# Endonasal_Module_Breakout_rev1.net
KiCad netlist of a schematic drawn in EAGLE
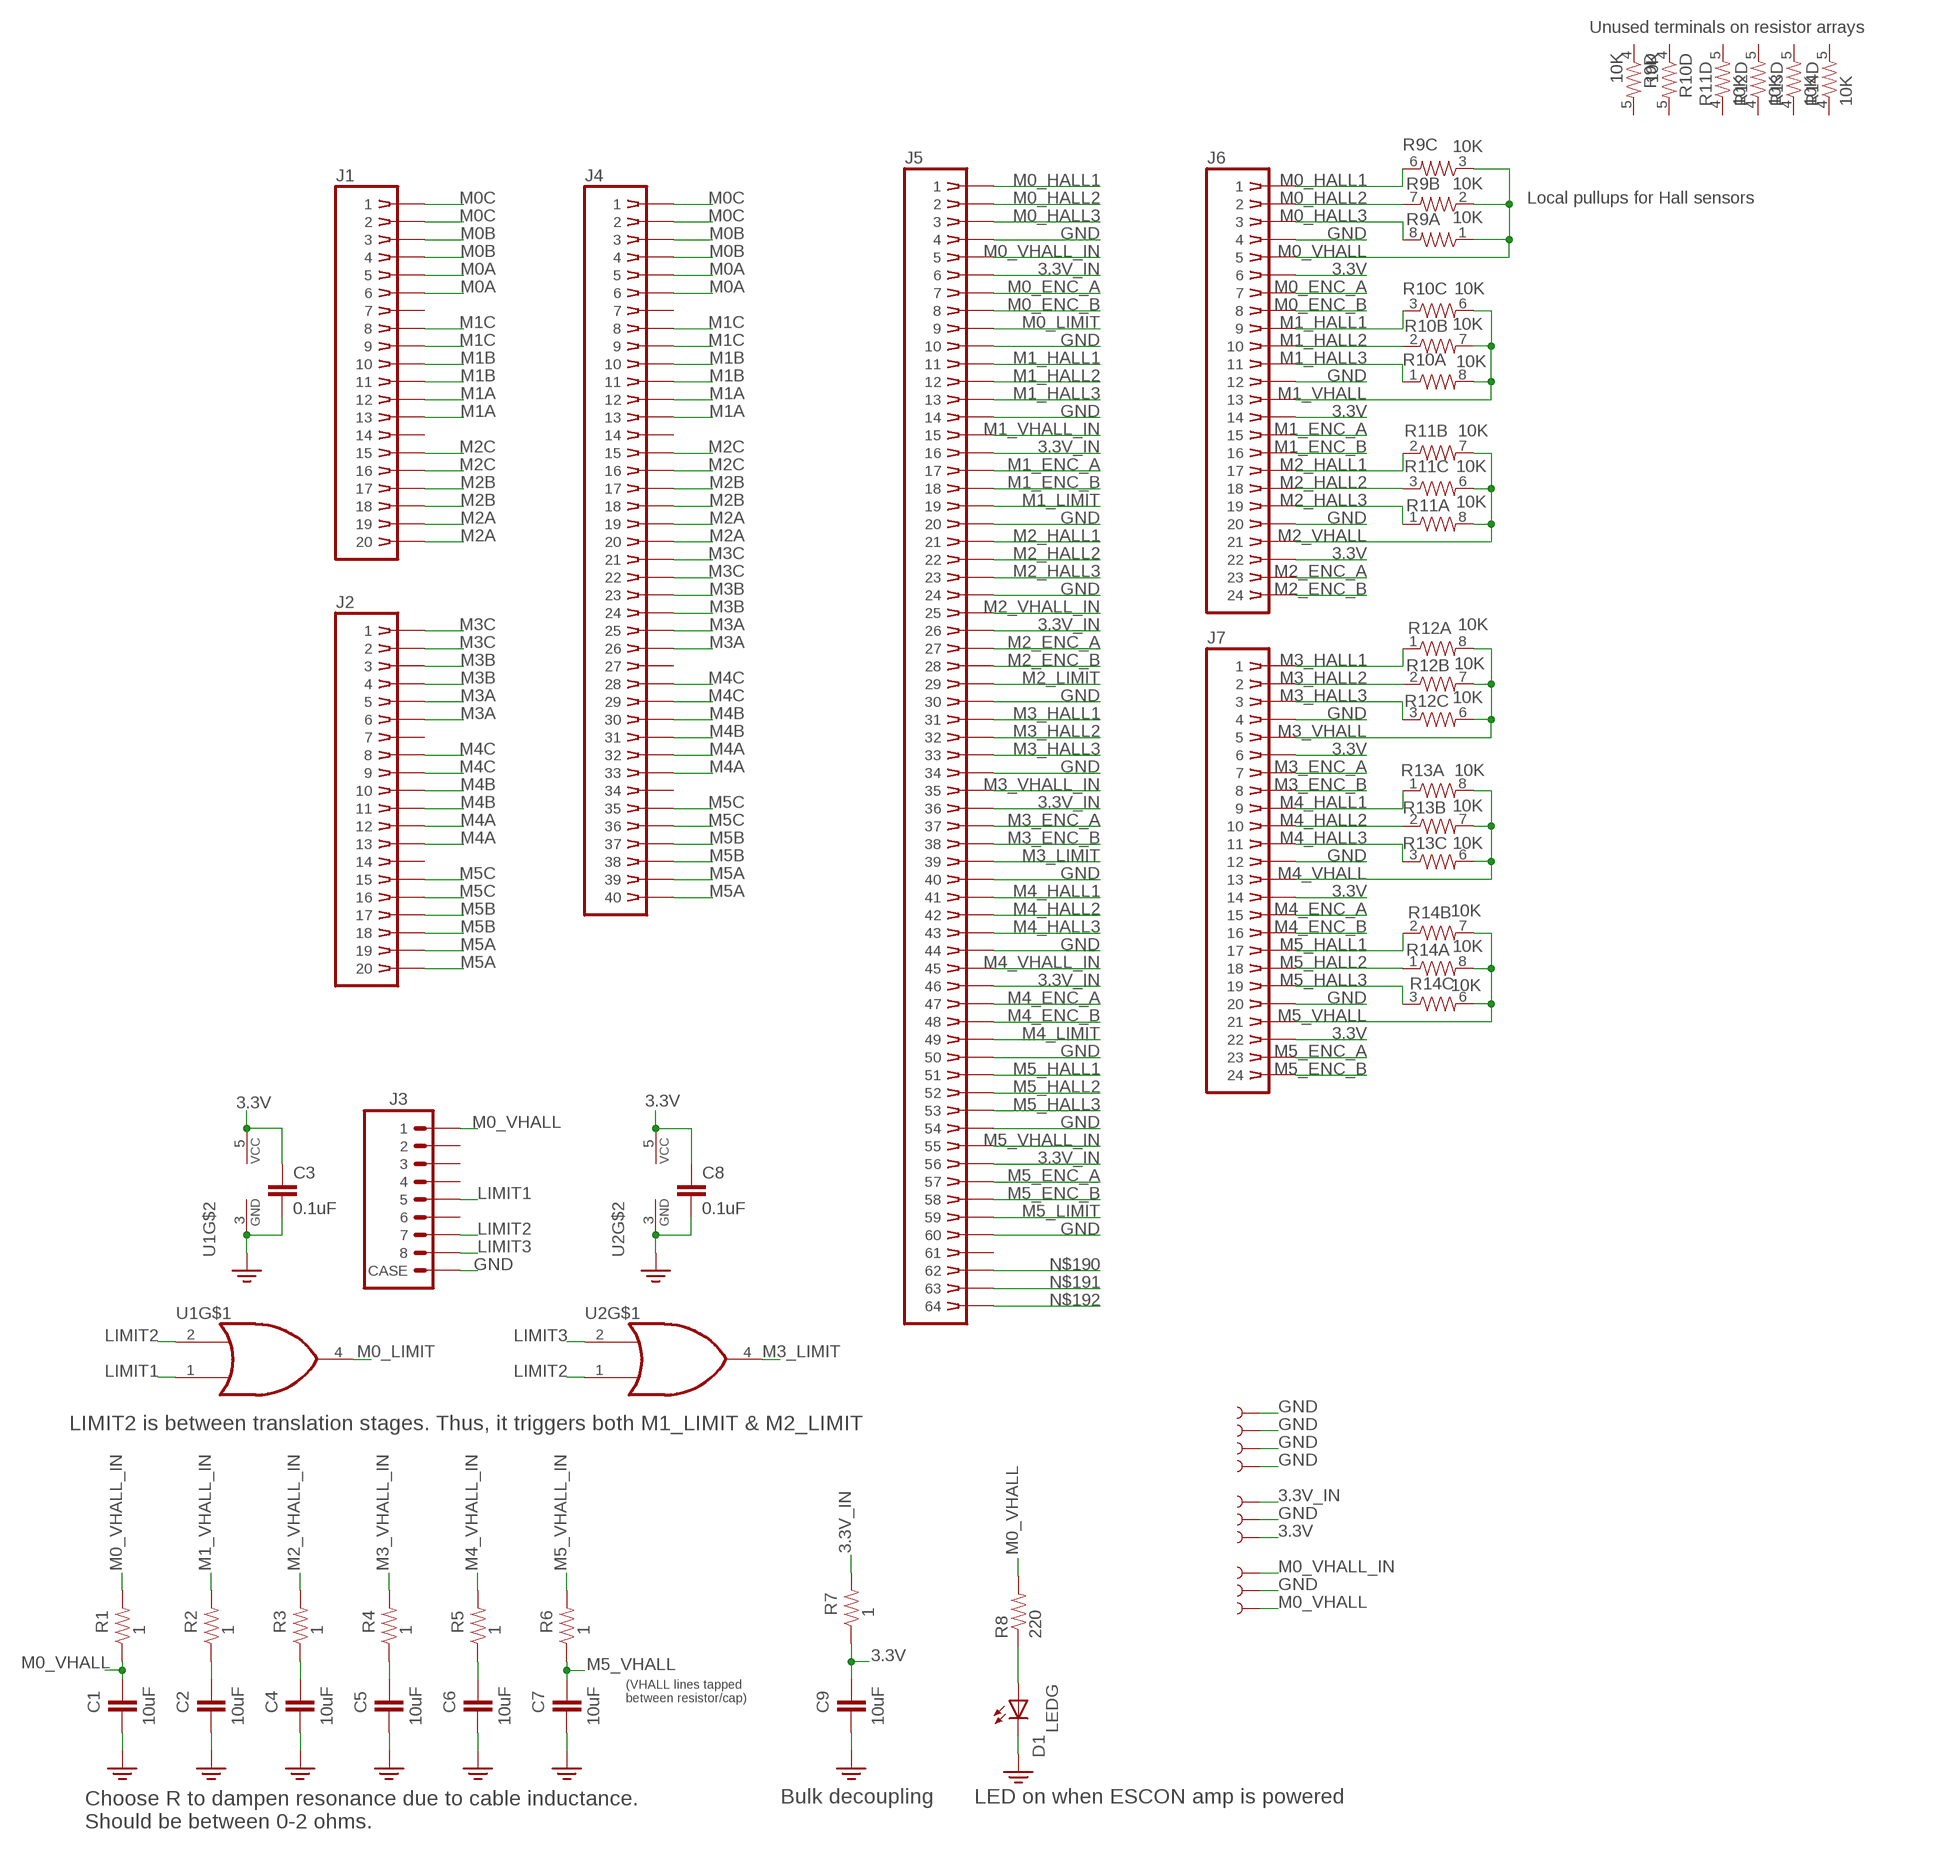
[diagram p0: schematic, sheet 1]

(export (version "E")
  (design (tool "Eeschema 10.0.6"))
  (components
    (comp (ref "3.3V")
      (value "TEST-POINT_5021")
      (footprint "eagle-import:TEST-POINT_5021")
      (libsource (lib "eagle-import") (part "TEST-POINT_5021"))
    )
    (comp (ref "3.3V-IN")
      (value "TEST-POINT_5021")
      (footprint "eagle-import:TEST-POINT_5021")
      (libsource (lib "eagle-import") (part "TEST-POINT_5021"))
    )
    (comp (ref "5V")
      (value "TEST-POINT_5021")
      (footprint "eagle-import:TEST-POINT_5021")
      (libsource (lib "eagle-import") (part "TEST-POINT_5021"))
    )
    (comp (ref "5V-IN")
      (value "TEST-POINT_5021")
      (footprint "eagle-import:TEST-POINT_5021")
      (libsource (lib "eagle-import") (part "TEST-POINT_5021"))
    )
    (comp (ref "C1")
      (value "10uF")
      (footprint "eagle-import:C0805K")
      (libsource (lib "eagle-import") (part "CAP0805"))
    )
    (comp (ref "C2")
      (value "10uF")
      (footprint "eagle-import:C0805K")
      (libsource (lib "eagle-import") (part "CAP0805"))
    )
    (comp (ref "C3")
      (value "0.1uF")
      (footprint "eagle-import:0603-CAP")
      (libsource (lib "eagle-import") (part "CAP0603-CAP"))
    )
    (comp (ref "C4")
      (value "10uF")
      (footprint "eagle-import:C0805K")
      (libsource (lib "eagle-import") (part "CAP0805"))
    )
    (comp (ref "C5")
      (value "10uF")
      (footprint "eagle-import:C0805K")
      (libsource (lib "eagle-import") (part "CAP0805"))
    )
    (comp (ref "C6")
      (value "10uF")
      (footprint "eagle-import:C0805K")
      (libsource (lib "eagle-import") (part "CAP0805"))
    )
    (comp (ref "C7")
      (value "10uF")
      (footprint "eagle-import:C0805K")
      (libsource (lib "eagle-import") (part "CAP0805"))
    )
    (comp (ref "C8")
      (value "0.1uF")
      (footprint "eagle-import:0603-CAP")
      (libsource (lib "eagle-import") (part "CAP0603-CAP"))
    )
    (comp (ref "C9")
      (value "10uF")
      (footprint "eagle-import:C0805K")
      (libsource (lib "eagle-import") (part "CAP0805"))
    )
    (comp (ref "D1")
      (value "LEDG")
      (footprint "eagle-import:LED-0805")
      (libsource (lib "eagle-import") (part "LED-0805"))
    )
    (comp (ref "GND")
      (value "TEST-POINT_5021")
      (footprint "eagle-import:TEST-POINT_5021")
      (libsource (lib "eagle-import") (part "TEST-POINT_5021"))
    )
    (comp (ref "J1")
      (value "CONN_RECT_2X10TH")
      (footprint "eagle-import:CONN_IDC_20_MALE_TH")
      (libsource (lib "eagle-import") (part "CONN_RECT_2X10TH"))
    )
    (comp (ref "J2")
      (value "CONN_RECT_2X10TH")
      (footprint "eagle-import:CONN_IDC_20_MALE_TH")
      (libsource (lib "eagle-import") (part "CONN_RECT_2X10TH"))
    )
    (comp (ref "J3")
      (value "JACK_8P8C_RJ45_ETHERNET")
      (footprint "eagle-import:ETHERNET_A104932")
      (libsource (lib "eagle-import") (part "JACK_8P8C_RJ45_ETHERNET"))
    )
    (comp (ref "J4")
      (value "CONN_RECT_2X20TH")
      (footprint "eagle-import:CONN_IDC_40_MALE_TH")
      (libsource (lib "eagle-import") (part "CONN_RECT_2X20TH"))
    )
    (comp (ref "J5")
      (value "CONN_RECT_2X32NOHOLES")
      (footprint "eagle-import:CONN_IDC_64_MALE_TH_NOHOLES")
      (libsource (lib "eagle-import") (part "CONN_RECT_2X32NOHOLES"))
    )
    (comp (ref "J6")
      (value "CONN_RECT_2X12TH")
      (footprint "eagle-import:CONN_IDC_24_MALE_TH")
      (libsource (lib "eagle-import") (part "CONN_RECT_2X12TH"))
    )
    (comp (ref "J7")
      (value "CONN_RECT_2X12TH")
      (footprint "eagle-import:CONN_IDC_24_MALE_TH")
      (libsource (lib "eagle-import") (part "CONN_RECT_2X12TH"))
    )
    (comp (ref "R1")
      (value "1")
      (footprint "eagle-import:0603-RES")
      (libsource (lib "eagle-import") (part "RESISTOR-0603"))
    )
    (comp (ref "R2")
      (value "1")
      (footprint "eagle-import:0603-RES")
      (libsource (lib "eagle-import") (part "RESISTOR-0603"))
    )
    (comp (ref "R3")
      (value "1")
      (footprint "eagle-import:0603-RES")
      (libsource (lib "eagle-import") (part "RESISTOR-0603"))
    )
    (comp (ref "R4")
      (value "1")
      (footprint "eagle-import:0603-RES")
      (libsource (lib "eagle-import") (part "RESISTOR-0603"))
    )
    (comp (ref "R5")
      (value "1")
      (footprint "eagle-import:0603-RES")
      (libsource (lib "eagle-import") (part "RESISTOR-0603"))
    )
    (comp (ref "R6")
      (value "1")
      (footprint "eagle-import:0603-RES")
      (libsource (lib "eagle-import") (part "RESISTOR-0603"))
    )
    (comp (ref "R7")
      (value "1")
      (footprint "eagle-import:0603-RES")
      (libsource (lib "eagle-import") (part "RESISTOR-0603"))
    )
    (comp (ref "R8")
      (value "220")
      (footprint "eagle-import:0603-RES")
      (libsource (lib "eagle-import") (part "RESISTOR-0603"))
    )
    (comp (ref "R9")
      (value "10K")
      (footprint "eagle-import:0603-ARV")
      (libsource (lib "eagle-import") (part "RESISTOR-ARRAY0603-ARV"))
    )
    (comp (ref "R10")
      (value "10K")
      (footprint "eagle-import:0603-ARV")
      (libsource (lib "eagle-import") (part "RESISTOR-ARRAY0603-ARV"))
    )
    (comp (ref "R11")
      (value "10K")
      (footprint "eagle-import:0603-ARV")
      (libsource (lib "eagle-import") (part "RESISTOR-ARRAY0603-ARV"))
    )
    (comp (ref "R12")
      (value "10K")
      (footprint "eagle-import:0603-ARV")
      (libsource (lib "eagle-import") (part "RESISTOR-ARRAY0603-ARV"))
    )
    (comp (ref "R13")
      (value "10K")
      (footprint "eagle-import:0603-ARV")
      (libsource (lib "eagle-import") (part "RESISTOR-ARRAY0603-ARV"))
    )
    (comp (ref "R14")
      (value "10K")
      (footprint "eagle-import:0603-ARV")
      (libsource (lib "eagle-import") (part "RESISTOR-ARRAY0603-ARV"))
    )
    (comp (ref "TP5")
      (value "TEST-POINT_5021")
      (footprint "eagle-import:TEST-POINT_5021")
      (libsource (lib "eagle-import") (part "TEST-POINT_5021"))
    )
    (comp (ref "TP7")
      (value "TEST-POINT3X5")
      (footprint "eagle-import:PAD.03X.05")
      (libsource (lib "eagle-import") (part "TEST-POINT3X5"))
    )
    (comp (ref "TP8")
      (value "TEST-POINT3X5")
      (footprint "eagle-import:PAD.03X.05")
      (libsource (lib "eagle-import") (part "TEST-POINT3X5"))
    )
    (comp (ref "TP9")
      (value "TEST-POINT3X5")
      (footprint "eagle-import:PAD.03X.05")
      (libsource (lib "eagle-import") (part "TEST-POINT3X5"))
    )
    (comp (ref "TP10")
      (value "TEST-POINT3X5")
      (footprint "eagle-import:PAD.03X.05")
      (libsource (lib "eagle-import") (part "TEST-POINT3X5"))
    )
    (comp (ref "U1")
      (value "OR_M0")
      (footprint "eagle-import:SOT353")
      (libsource (lib "eagle-import") (part "OR"))
    )
    (comp (ref "U2")
      (value "OR_M3")
      (footprint "eagle-import:SOT353")
      (libsource (lib "eagle-import") (part "OR"))
    )
  )
  (nets
    (net (code "1") (name "/3.3V") (class "Default")
      (node (ref "3.3V") (pin "P$1") (pinfunction "1_P$1") (pintype "bidirectional"))
      (node (ref "C3") (pin "1") (pinfunction "1_1") (pintype "passive"))
      (node (ref "C8") (pin "1") (pinfunction "1_1") (pintype "passive"))
      (node (ref "C9") (pin "1") (pinfunction "1_1") (pintype "passive"))
      (node (ref "J6") (pin "P$14") (pinfunction "14_P$14") (pintype "passive"))
      (node (ref "J6") (pin "P$22") (pinfunction "22_P$22") (pintype "passive"))
      (node (ref "J6") (pin "P$6") (pinfunction "6_P$6") (pintype "passive"))
      (node (ref "J7") (pin "P$14") (pinfunction "14_P$14") (pintype "passive"))
      (node (ref "J7") (pin "P$22") (pinfunction "22_P$22") (pintype "passive"))
      (node (ref "J7") (pin "P$6") (pinfunction "6_P$6") (pintype "passive"))
      (node (ref "R7") (pin "1") (pinfunction "1_1") (pintype "passive"))
      (node (ref "U1") (pin "5") (pinfunction "VCC_5") (pintype "power_in"))
      (node (ref "U2") (pin "5") (pinfunction "VCC_5") (pintype "power_in"))
    )
    (net (code "2") (name "/3.3V_IN") (class "Default")
      (node (ref "3.3V-IN") (pin "P$1") (pinfunction "1_P$1") (pintype "bidirectional"))
      (node (ref "J5") (pin "P$16") (pinfunction "16_P$16") (pintype "passive"))
      (node (ref "J5") (pin "P$26") (pinfunction "26_P$26") (pintype "passive"))
      (node (ref "J5") (pin "P$36") (pinfunction "36_P$36") (pintype "passive"))
      (node (ref "J5") (pin "P$46") (pinfunction "46_P$46") (pintype "passive"))
      (node (ref "J5") (pin "P$56") (pinfunction "56_P$56") (pintype "passive"))
      (node (ref "J5") (pin "P$6") (pinfunction "6_P$6") (pintype "passive"))
      (node (ref "R7") (pin "2") (pinfunction "2_2") (pintype "passive"))
    )
    (net (code "3") (name "/LIMIT1") (class "Default")
      (node (ref "J3") (pin "P$5") (pinfunction "5_P$5") (pintype "passive"))
      (node (ref "U1") (pin "1") (pinfunction "B_1") (pintype "input"))
    )
    (net (code "4") (name "/LIMIT2") (class "Default")
      (node (ref "J3") (pin "P$7") (pinfunction "7_P$7") (pintype "passive"))
      (node (ref "U1") (pin "2") (pinfunction "A_2") (pintype "input"))
      (node (ref "U2") (pin "1") (pinfunction "B_1") (pintype "input"))
    )
    (net (code "5") (name "/LIMIT3") (class "Default")
      (node (ref "J3") (pin "P$8") (pinfunction "8_P$8") (pintype "passive"))
      (node (ref "U2") (pin "2") (pinfunction "A_2") (pintype "input"))
    )
    (net (code "6") (name "/M0A") (class "Default")
      (node (ref "J1") (pin "P$5") (pinfunction "5_P$5") (pintype "passive"))
      (node (ref "J1") (pin "P$6") (pinfunction "6_P$6") (pintype "passive"))
      (node (ref "J4") (pin "P$5") (pinfunction "5_P$5") (pintype "passive"))
      (node (ref "J4") (pin "P$6") (pinfunction "6_P$6") (pintype "passive"))
    )
    (net (code "7") (name "/M0B") (class "Default")
      (node (ref "J1") (pin "P$3") (pinfunction "3_P$3") (pintype "passive"))
      (node (ref "J1") (pin "P$4") (pinfunction "4_P$4") (pintype "passive"))
      (node (ref "J4") (pin "P$3") (pinfunction "3_P$3") (pintype "passive"))
      (node (ref "J4") (pin "P$4") (pinfunction "4_P$4") (pintype "passive"))
    )
    (net (code "8") (name "/M0C") (class "Default")
      (node (ref "J1") (pin "P$1") (pinfunction "1_P$1") (pintype "passive"))
      (node (ref "J1") (pin "P$2") (pinfunction "2_P$2") (pintype "passive"))
      (node (ref "J4") (pin "P$1") (pinfunction "1_P$1") (pintype "passive"))
      (node (ref "J4") (pin "P$2") (pinfunction "2_P$2") (pintype "passive"))
    )
    (net (code "9") (name "/M0_ENC_A") (class "Default")
      (node (ref "J5") (pin "P$7") (pinfunction "7_P$7") (pintype "passive"))
      (node (ref "J6") (pin "P$7") (pinfunction "7_P$7") (pintype "passive"))
    )
    (net (code "10") (name "/M0_ENC_B") (class "Default")
      (node (ref "J5") (pin "P$8") (pinfunction "8_P$8") (pintype "passive"))
      (node (ref "J6") (pin "P$8") (pinfunction "8_P$8") (pintype "passive"))
    )
    (net (code "11") (name "/M0_HALL1") (class "Default")
      (node (ref "J5") (pin "P$1") (pinfunction "1_P$1") (pintype "passive"))
      (node (ref "J6") (pin "P$1") (pinfunction "1_P$1") (pintype "passive"))
      (node (ref "R9") (pin "6") (pinfunction "2_6") (pintype "passive"))
    )
    (net (code "12") (name "/M0_HALL2") (class "Default")
      (node (ref "J5") (pin "P$2") (pinfunction "2_P$2") (pintype "passive"))
      (node (ref "J6") (pin "P$2") (pinfunction "2_P$2") (pintype "passive"))
      (node (ref "R9") (pin "7") (pinfunction "2_7") (pintype "passive"))
    )
    (net (code "13") (name "/M0_HALL3") (class "Default")
      (node (ref "J5") (pin "P$3") (pinfunction "3_P$3") (pintype "passive"))
      (node (ref "J6") (pin "P$3") (pinfunction "3_P$3") (pintype "passive"))
      (node (ref "R9") (pin "8") (pinfunction "2_8") (pintype "passive"))
    )
    (net (code "14") (name "/M0_LIMIT") (class "Default")
      (node (ref "J5") (pin "P$9") (pinfunction "9_P$9") (pintype "passive"))
      (node (ref "U1") (pin "4") (pinfunction "Y_4") (pintype "output"))
    )
    (net (code "15") (name "/M0_VHALL") (class "Default")
      (node (ref "5V") (pin "P$1") (pinfunction "1_P$1") (pintype "bidirectional"))
      (node (ref "C1") (pin "1") (pinfunction "1_1") (pintype "passive"))
      (node (ref "J3") (pin "P$1") (pinfunction "1_P$1") (pintype "passive"))
      (node (ref "J6") (pin "P$5") (pinfunction "5_P$5") (pintype "passive"))
      (node (ref "R1") (pin "1") (pinfunction "1_1") (pintype "passive"))
      (node (ref "R8") (pin "2") (pinfunction "2_2") (pintype "passive"))
      (node (ref "R9") (pin "1") (pinfunction "1_1") (pintype "passive"))
      (node (ref "R9") (pin "2") (pinfunction "1_2") (pintype "passive"))
      (node (ref "R9") (pin "3") (pinfunction "1_3") (pintype "passive"))
    )
    (net (code "16") (name "/M0_VHALL_IN") (class "Default")
      (node (ref "5V-IN") (pin "P$1") (pinfunction "1_P$1") (pintype "bidirectional"))
      (node (ref "J5") (pin "P$5") (pinfunction "5_P$5") (pintype "passive"))
      (node (ref "R1") (pin "2") (pinfunction "2_2") (pintype "passive"))
    )
    (net (code "17") (name "/M1A") (class "Default")
      (node (ref "J1") (pin "P$12") (pinfunction "12_P$12") (pintype "passive"))
      (node (ref "J1") (pin "P$13") (pinfunction "13_P$13") (pintype "passive"))
      (node (ref "J4") (pin "P$12") (pinfunction "12_P$12") (pintype "passive"))
      (node (ref "J4") (pin "P$13") (pinfunction "13_P$13") (pintype "passive"))
    )
    (net (code "18") (name "/M1B") (class "Default")
      (node (ref "J1") (pin "P$10") (pinfunction "10_P$10") (pintype "passive"))
      (node (ref "J1") (pin "P$11") (pinfunction "11_P$11") (pintype "passive"))
      (node (ref "J4") (pin "P$10") (pinfunction "10_P$10") (pintype "passive"))
      (node (ref "J4") (pin "P$11") (pinfunction "11_P$11") (pintype "passive"))
    )
    (net (code "19") (name "/M1C") (class "Default")
      (node (ref "J1") (pin "P$8") (pinfunction "8_P$8") (pintype "passive"))
      (node (ref "J1") (pin "P$9") (pinfunction "9_P$9") (pintype "passive"))
      (node (ref "J4") (pin "P$8") (pinfunction "8_P$8") (pintype "passive"))
      (node (ref "J4") (pin "P$9") (pinfunction "9_P$9") (pintype "passive"))
    )
    (net (code "20") (name "/M1_ENC_A") (class "Default")
      (node (ref "J5") (pin "P$17") (pinfunction "17_P$17") (pintype "passive"))
      (node (ref "J6") (pin "P$15") (pinfunction "15_P$15") (pintype "passive"))
    )
    (net (code "21") (name "/M1_ENC_B") (class "Default")
      (node (ref "J5") (pin "P$18") (pinfunction "18_P$18") (pintype "passive"))
      (node (ref "J6") (pin "P$16") (pinfunction "16_P$16") (pintype "passive"))
    )
    (net (code "22") (name "/M1_HALL1") (class "Default")
      (node (ref "J5") (pin "P$11") (pinfunction "11_P$11") (pintype "passive"))
      (node (ref "J6") (pin "P$9") (pinfunction "9_P$9") (pintype "passive"))
      (node (ref "R10") (pin "3") (pinfunction "1_3") (pintype "passive"))
    )
    (net (code "23") (name "/M1_HALL2") (class "Default")
      (node (ref "J5") (pin "P$12") (pinfunction "12_P$12") (pintype "passive"))
      (node (ref "J6") (pin "P$10") (pinfunction "10_P$10") (pintype "passive"))
      (node (ref "R10") (pin "2") (pinfunction "1_2") (pintype "passive"))
    )
    (net (code "24") (name "/M1_HALL3") (class "Default")
      (node (ref "J5") (pin "P$13") (pinfunction "13_P$13") (pintype "passive"))
      (node (ref "J6") (pin "P$11") (pinfunction "11_P$11") (pintype "passive"))
      (node (ref "R10") (pin "1") (pinfunction "1_1") (pintype "passive"))
    )
    (net (code "25") (name "/M1_LIMIT") (class "Default")
      (node (ref "J5") (pin "P$19") (pinfunction "19_P$19") (pintype "passive"))
    )
    (net (code "26") (name "/M1_VHALL") (class "Default")
      (node (ref "C2") (pin "1") (pinfunction "1_1") (pintype "passive"))
      (node (ref "J6") (pin "P$13") (pinfunction "13_P$13") (pintype "passive"))
      (node (ref "R10") (pin "6") (pinfunction "2_6") (pintype "passive"))
      (node (ref "R10") (pin "7") (pinfunction "2_7") (pintype "passive"))
      (node (ref "R10") (pin "8") (pinfunction "2_8") (pintype "passive"))
      (node (ref "R2") (pin "1") (pinfunction "1_1") (pintype "passive"))
    )
    (net (code "27") (name "/M1_VHALL_IN") (class "Default")
      (node (ref "J5") (pin "P$15") (pinfunction "15_P$15") (pintype "passive"))
      (node (ref "R2") (pin "2") (pinfunction "2_2") (pintype "passive"))
    )
    (net (code "28") (name "/M2A") (class "Default")
      (node (ref "J1") (pin "P$19") (pinfunction "19_P$19") (pintype "passive"))
      (node (ref "J1") (pin "P$20") (pinfunction "20_P$20") (pintype "passive"))
      (node (ref "J4") (pin "P$19") (pinfunction "19_P$19") (pintype "passive"))
      (node (ref "J4") (pin "P$20") (pinfunction "20_P$20") (pintype "passive"))
    )
    (net (code "29") (name "/M2B") (class "Default")
      (node (ref "J1") (pin "P$17") (pinfunction "17_P$17") (pintype "passive"))
      (node (ref "J1") (pin "P$18") (pinfunction "18_P$18") (pintype "passive"))
      (node (ref "J4") (pin "P$17") (pinfunction "17_P$17") (pintype "passive"))
      (node (ref "J4") (pin "P$18") (pinfunction "18_P$18") (pintype "passive"))
    )
    (net (code "30") (name "/M2C") (class "Default")
      (node (ref "J1") (pin "P$15") (pinfunction "15_P$15") (pintype "passive"))
      (node (ref "J1") (pin "P$16") (pinfunction "16_P$16") (pintype "passive"))
      (node (ref "J4") (pin "P$15") (pinfunction "15_P$15") (pintype "passive"))
      (node (ref "J4") (pin "P$16") (pinfunction "16_P$16") (pintype "passive"))
    )
    (net (code "31") (name "/M2_ENC_A") (class "Default")
      (node (ref "J5") (pin "P$27") (pinfunction "27_P$27") (pintype "passive"))
      (node (ref "J6") (pin "P$23") (pinfunction "23_P$23") (pintype "passive"))
    )
    (net (code "32") (name "/M2_ENC_B") (class "Default")
      (node (ref "J5") (pin "P$28") (pinfunction "28_P$28") (pintype "passive"))
      (node (ref "J6") (pin "P$24") (pinfunction "24_P$24") (pintype "passive"))
    )
    (net (code "33") (name "/M2_HALL1") (class "Default")
      (node (ref "J5") (pin "P$21") (pinfunction "21_P$21") (pintype "passive"))
      (node (ref "J6") (pin "P$17") (pinfunction "17_P$17") (pintype "passive"))
      (node (ref "R11") (pin "2") (pinfunction "1_2") (pintype "passive"))
    )
    (net (code "34") (name "/M2_HALL2") (class "Default")
      (node (ref "J5") (pin "P$22") (pinfunction "22_P$22") (pintype "passive"))
      (node (ref "J6") (pin "P$18") (pinfunction "18_P$18") (pintype "passive"))
      (node (ref "R11") (pin "3") (pinfunction "1_3") (pintype "passive"))
    )
    (net (code "35") (name "/M2_HALL3") (class "Default")
      (node (ref "J5") (pin "P$23") (pinfunction "23_P$23") (pintype "passive"))
      (node (ref "J6") (pin "P$19") (pinfunction "19_P$19") (pintype "passive"))
      (node (ref "R11") (pin "1") (pinfunction "1_1") (pintype "passive"))
    )
    (net (code "36") (name "/M2_LIMIT") (class "Default")
      (node (ref "J5") (pin "P$29") (pinfunction "29_P$29") (pintype "passive"))
    )
    (net (code "37") (name "/M2_VHALL") (class "Default")
      (node (ref "C4") (pin "1") (pinfunction "1_1") (pintype "passive"))
      (node (ref "J6") (pin "P$21") (pinfunction "21_P$21") (pintype "passive"))
      (node (ref "R11") (pin "6") (pinfunction "2_6") (pintype "passive"))
      (node (ref "R11") (pin "7") (pinfunction "2_7") (pintype "passive"))
      (node (ref "R11") (pin "8") (pinfunction "2_8") (pintype "passive"))
      (node (ref "R3") (pin "1") (pinfunction "1_1") (pintype "passive"))
    )
    (net (code "38") (name "/M2_VHALL_IN") (class "Default")
      (node (ref "J5") (pin "P$25") (pinfunction "25_P$25") (pintype "passive"))
      (node (ref "R3") (pin "2") (pinfunction "2_2") (pintype "passive"))
    )
    (net (code "39") (name "/M3A") (class "Default")
      (node (ref "J2") (pin "P$5") (pinfunction "5_P$5") (pintype "passive"))
      (node (ref "J2") (pin "P$6") (pinfunction "6_P$6") (pintype "passive"))
      (node (ref "J4") (pin "P$25") (pinfunction "25_P$25") (pintype "passive"))
      (node (ref "J4") (pin "P$26") (pinfunction "26_P$26") (pintype "passive"))
    )
    (net (code "40") (name "/M3B") (class "Default")
      (node (ref "J2") (pin "P$3") (pinfunction "3_P$3") (pintype "passive"))
      (node (ref "J2") (pin "P$4") (pinfunction "4_P$4") (pintype "passive"))
      (node (ref "J4") (pin "P$23") (pinfunction "23_P$23") (pintype "passive"))
      (node (ref "J4") (pin "P$24") (pinfunction "24_P$24") (pintype "passive"))
    )
    (net (code "41") (name "/M3C") (class "Default")
      (node (ref "J2") (pin "P$1") (pinfunction "1_P$1") (pintype "passive"))
      (node (ref "J2") (pin "P$2") (pinfunction "2_P$2") (pintype "passive"))
      (node (ref "J4") (pin "P$21") (pinfunction "21_P$21") (pintype "passive"))
      (node (ref "J4") (pin "P$22") (pinfunction "22_P$22") (pintype "passive"))
    )
    (net (code "42") (name "/M3_ENC_A") (class "Default")
      (node (ref "J5") (pin "P$37") (pinfunction "37_P$37") (pintype "passive"))
      (node (ref "J7") (pin "P$7") (pinfunction "7_P$7") (pintype "passive"))
    )
    (net (code "43") (name "/M3_ENC_B") (class "Default")
      (node (ref "J5") (pin "P$38") (pinfunction "38_P$38") (pintype "passive"))
      (node (ref "J7") (pin "P$8") (pinfunction "8_P$8") (pintype "passive"))
    )
    (net (code "44") (name "/M3_HALL1") (class "Default")
      (node (ref "J5") (pin "P$31") (pinfunction "31_P$31") (pintype "passive"))
      (node (ref "J7") (pin "P$1") (pinfunction "1_P$1") (pintype "passive"))
      (node (ref "R12") (pin "1") (pinfunction "1_1") (pintype "passive"))
    )
    (net (code "45") (name "/M3_HALL2") (class "Default")
      (node (ref "J5") (pin "P$32") (pinfunction "32_P$32") (pintype "passive"))
      (node (ref "J7") (pin "P$2") (pinfunction "2_P$2") (pintype "passive"))
      (node (ref "R12") (pin "2") (pinfunction "1_2") (pintype "passive"))
    )
    (net (code "46") (name "/M3_HALL3") (class "Default")
      (node (ref "J5") (pin "P$33") (pinfunction "33_P$33") (pintype "passive"))
      (node (ref "J7") (pin "P$3") (pinfunction "3_P$3") (pintype "passive"))
      (node (ref "R12") (pin "3") (pinfunction "1_3") (pintype "passive"))
    )
    (net (code "47") (name "/M3_LIMIT") (class "Default")
      (node (ref "J5") (pin "P$39") (pinfunction "39_P$39") (pintype "passive"))
      (node (ref "U2") (pin "4") (pinfunction "Y_4") (pintype "output"))
    )
    (net (code "48") (name "/M3_VHALL") (class "Default")
      (node (ref "C5") (pin "1") (pinfunction "1_1") (pintype "passive"))
      (node (ref "J7") (pin "P$5") (pinfunction "5_P$5") (pintype "passive"))
      (node (ref "R12") (pin "6") (pinfunction "2_6") (pintype "passive"))
      (node (ref "R12") (pin "7") (pinfunction "2_7") (pintype "passive"))
      (node (ref "R12") (pin "8") (pinfunction "2_8") (pintype "passive"))
      (node (ref "R4") (pin "1") (pinfunction "1_1") (pintype "passive"))
    )
    (net (code "49") (name "/M3_VHALL_IN") (class "Default")
      (node (ref "J5") (pin "P$35") (pinfunction "35_P$35") (pintype "passive"))
      (node (ref "R4") (pin "2") (pinfunction "2_2") (pintype "passive"))
    )
    (net (code "50") (name "/M4A") (class "Default")
      (node (ref "J2") (pin "P$12") (pinfunction "12_P$12") (pintype "passive"))
      (node (ref "J2") (pin "P$13") (pinfunction "13_P$13") (pintype "passive"))
      (node (ref "J4") (pin "P$32") (pinfunction "32_P$32") (pintype "passive"))
      (node (ref "J4") (pin "P$33") (pinfunction "33_P$33") (pintype "passive"))
    )
    (net (code "51") (name "/M4B") (class "Default")
      (node (ref "J2") (pin "P$10") (pinfunction "10_P$10") (pintype "passive"))
      (node (ref "J2") (pin "P$11") (pinfunction "11_P$11") (pintype "passive"))
      (node (ref "J4") (pin "P$30") (pinfunction "30_P$30") (pintype "passive"))
      (node (ref "J4") (pin "P$31") (pinfunction "31_P$31") (pintype "passive"))
    )
    (net (code "52") (name "/M4C") (class "Default")
      (node (ref "J2") (pin "P$8") (pinfunction "8_P$8") (pintype "passive"))
      (node (ref "J2") (pin "P$9") (pinfunction "9_P$9") (pintype "passive"))
      (node (ref "J4") (pin "P$28") (pinfunction "28_P$28") (pintype "passive"))
      (node (ref "J4") (pin "P$29") (pinfunction "29_P$29") (pintype "passive"))
    )
    (net (code "53") (name "/M4_ENC_A") (class "Default")
      (node (ref "J5") (pin "P$47") (pinfunction "47_P$47") (pintype "passive"))
      (node (ref "J7") (pin "P$15") (pinfunction "15_P$15") (pintype "passive"))
    )
    (net (code "54") (name "/M4_ENC_B") (class "Default")
      (node (ref "J5") (pin "P$48") (pinfunction "48_P$48") (pintype "passive"))
      (node (ref "J7") (pin "P$16") (pinfunction "16_P$16") (pintype "passive"))
    )
    (net (code "55") (name "/M4_HALL1") (class "Default")
      (node (ref "J5") (pin "P$41") (pinfunction "41_P$41") (pintype "passive"))
      (node (ref "J7") (pin "P$9") (pinfunction "9_P$9") (pintype "passive"))
      (node (ref "R13") (pin "1") (pinfunction "1_1") (pintype "passive"))
    )
    (net (code "56") (name "/M4_HALL2") (class "Default")
      (node (ref "J5") (pin "P$42") (pinfunction "42_P$42") (pintype "passive"))
      (node (ref "J7") (pin "P$10") (pinfunction "10_P$10") (pintype "passive"))
      (node (ref "R13") (pin "2") (pinfunction "1_2") (pintype "passive"))
    )
    (net (code "57") (name "/M4_HALL3") (class "Default")
      (node (ref "J5") (pin "P$43") (pinfunction "43_P$43") (pintype "passive"))
      (node (ref "J7") (pin "P$11") (pinfunction "11_P$11") (pintype "passive"))
      (node (ref "R13") (pin "3") (pinfunction "1_3") (pintype "passive"))
    )
    (net (code "58") (name "/M4_LIMIT") (class "Default")
      (node (ref "J5") (pin "P$49") (pinfunction "49_P$49") (pintype "passive"))
    )
    (net (code "59") (name "/M4_VHALL") (class "Default")
      (node (ref "C6") (pin "1") (pinfunction "1_1") (pintype "passive"))
      (node (ref "J7") (pin "P$13") (pinfunction "13_P$13") (pintype "passive"))
      (node (ref "R13") (pin "6") (pinfunction "2_6") (pintype "passive"))
      (node (ref "R13") (pin "7") (pinfunction "2_7") (pintype "passive"))
      (node (ref "R13") (pin "8") (pinfunction "2_8") (pintype "passive"))
      (node (ref "R5") (pin "1") (pinfunction "1_1") (pintype "passive"))
    )
    (net (code "60") (name "/M4_VHALL_IN") (class "Default")
      (node (ref "J5") (pin "P$45") (pinfunction "45_P$45") (pintype "passive"))
      (node (ref "R5") (pin "2") (pinfunction "2_2") (pintype "passive"))
    )
    (net (code "61") (name "/M5A") (class "Default")
      (node (ref "J2") (pin "P$19") (pinfunction "19_P$19") (pintype "passive"))
      (node (ref "J2") (pin "P$20") (pinfunction "20_P$20") (pintype "passive"))
      (node (ref "J4") (pin "P$39") (pinfunction "39_P$39") (pintype "passive"))
      (node (ref "J4") (pin "P$40") (pinfunction "40_P$40") (pintype "passive"))
    )
    (net (code "62") (name "/M5B") (class "Default")
      (node (ref "J2") (pin "P$17") (pinfunction "17_P$17") (pintype "passive"))
      (node (ref "J2") (pin "P$18") (pinfunction "18_P$18") (pintype "passive"))
      (node (ref "J4") (pin "P$37") (pinfunction "37_P$37") (pintype "passive"))
      (node (ref "J4") (pin "P$38") (pinfunction "38_P$38") (pintype "passive"))
    )
    (net (code "63") (name "/M5C") (class "Default")
      (node (ref "J2") (pin "P$15") (pinfunction "15_P$15") (pintype "passive"))
      (node (ref "J2") (pin "P$16") (pinfunction "16_P$16") (pintype "passive"))
      (node (ref "J4") (pin "P$35") (pinfunction "35_P$35") (pintype "passive"))
      (node (ref "J4") (pin "P$36") (pinfunction "36_P$36") (pintype "passive"))
    )
    (net (code "64") (name "/M5_ENC_A") (class "Default")
      (node (ref "J5") (pin "P$57") (pinfunction "57_P$57") (pintype "passive"))
      (node (ref "J7") (pin "P$23") (pinfunction "23_P$23") (pintype "passive"))
    )
    (net (code "65") (name "/M5_ENC_B") (class "Default")
      (node (ref "J5") (pin "P$58") (pinfunction "58_P$58") (pintype "passive"))
      (node (ref "J7") (pin "P$24") (pinfunction "24_P$24") (pintype "passive"))
    )
    (net (code "66") (name "/M5_HALL1") (class "Default")
      (node (ref "J5") (pin "P$51") (pinfunction "51_P$51") (pintype "passive"))
      (node (ref "J7") (pin "P$17") (pinfunction "17_P$17") (pintype "passive"))
      (node (ref "R14") (pin "2") (pinfunction "1_2") (pintype "passive"))
    )
    (net (code "67") (name "/M5_HALL2") (class "Default")
      (node (ref "J5") (pin "P$52") (pinfunction "52_P$52") (pintype "passive"))
      (node (ref "J7") (pin "P$18") (pinfunction "18_P$18") (pintype "passive"))
      (node (ref "R14") (pin "1") (pinfunction "1_1") (pintype "passive"))
    )
    (net (code "68") (name "/M5_HALL3") (class "Default")
      (node (ref "J5") (pin "P$53") (pinfunction "53_P$53") (pintype "passive"))
      (node (ref "J7") (pin "P$19") (pinfunction "19_P$19") (pintype "passive"))
      (node (ref "R14") (pin "3") (pinfunction "1_3") (pintype "passive"))
    )
    (net (code "69") (name "/M5_LIMIT") (class "Default")
      (node (ref "J5") (pin "P$59") (pinfunction "59_P$59") (pintype "passive"))
    )
    (net (code "70") (name "/M5_VHALL") (class "Default")
      (node (ref "C7") (pin "1") (pinfunction "1_1") (pintype "passive"))
      (node (ref "J7") (pin "P$21") (pinfunction "21_P$21") (pintype "passive"))
      (node (ref "R14") (pin "6") (pinfunction "2_6") (pintype "passive"))
      (node (ref "R14") (pin "7") (pinfunction "2_7") (pintype "passive"))
      (node (ref "R14") (pin "8") (pinfunction "2_8") (pintype "passive"))
      (node (ref "R6") (pin "1") (pinfunction "1_1") (pintype "passive"))
    )
    (net (code "71") (name "/M5_VHALL_IN") (class "Default")
      (node (ref "J5") (pin "P$55") (pinfunction "55_P$55") (pintype "passive"))
      (node (ref "R6") (pin "2") (pinfunction "2_2") (pintype "passive"))
    )
    (net (code "72") (name "/N$190") (class "Default")
      (node (ref "J5") (pin "P$62") (pinfunction "62_P$62") (pintype "passive"))
    )
    (net (code "73") (name "/N$191") (class "Default")
      (node (ref "J5") (pin "P$63") (pinfunction "63_P$63") (pintype "passive"))
    )
    (net (code "74") (name "/N$192") (class "Default")
      (node (ref "J5") (pin "P$64") (pinfunction "64_P$64") (pintype "passive"))
    )
    (net (code "75") (name "GND2") (class "Default")
      (node (ref "C1") (pin "2") (pinfunction "2_2") (pintype "passive"))
      (node (ref "C2") (pin "2") (pinfunction "2_2") (pintype "passive"))
      (node (ref "C3") (pin "2") (pinfunction "2_2") (pintype "passive"))
      (node (ref "C4") (pin "2") (pinfunction "2_2") (pintype "passive"))
      (node (ref "C5") (pin "2") (pinfunction "2_2") (pintype "passive"))
      (node (ref "C6") (pin "2") (pinfunction "2_2") (pintype "passive"))
      (node (ref "C7") (pin "2") (pinfunction "2_2") (pintype "passive"))
      (node (ref "C8") (pin "2") (pinfunction "2_2") (pintype "passive"))
      (node (ref "C9") (pin "2") (pinfunction "2_2") (pintype "passive"))
      (node (ref "D1") (pin "C") (pinfunction "C_C") (pintype "passive"))
      (node (ref "GND") (pin "P$1") (pinfunction "1_P$1") (pintype "bidirectional"))
      (node (ref "J3") (pin "SHIELD1") (pinfunction "CASE_SHIELD1") (pintype "passive"))
      (node (ref "J3") (pin "SHIELD2") (pinfunction "CASE_SHIELD2") (pintype "passive"))
      (node (ref "J5") (pin "P$10") (pinfunction "10_P$10") (pintype "passive"))
      (node (ref "J5") (pin "P$14") (pinfunction "14_P$14") (pintype "passive"))
      (node (ref "J5") (pin "P$20") (pinfunction "20_P$20") (pintype "passive"))
      (node (ref "J5") (pin "P$24") (pinfunction "24_P$24") (pintype "passive"))
      (node (ref "J5") (pin "P$30") (pinfunction "30_P$30") (pintype "passive"))
      (node (ref "J5") (pin "P$34") (pinfunction "34_P$34") (pintype "passive"))
      (node (ref "J5") (pin "P$4") (pinfunction "4_P$4") (pintype "passive"))
      (node (ref "J5") (pin "P$40") (pinfunction "40_P$40") (pintype "passive"))
      (node (ref "J5") (pin "P$44") (pinfunction "44_P$44") (pintype "passive"))
      (node (ref "J5") (pin "P$50") (pinfunction "50_P$50") (pintype "passive"))
      (node (ref "J5") (pin "P$54") (pinfunction "54_P$54") (pintype "passive"))
      (node (ref "J5") (pin "P$60") (pinfunction "60_P$60") (pintype "passive"))
      (node (ref "J6") (pin "P$12") (pinfunction "12_P$12") (pintype "passive"))
      (node (ref "J6") (pin "P$20") (pinfunction "20_P$20") (pintype "passive"))
      (node (ref "J6") (pin "P$4") (pinfunction "4_P$4") (pintype "passive"))
      (node (ref "J7") (pin "P$12") (pinfunction "12_P$12") (pintype "passive"))
      (node (ref "J7") (pin "P$20") (pinfunction "20_P$20") (pintype "passive"))
      (node (ref "J7") (pin "P$4") (pinfunction "4_P$4") (pintype "passive"))
      (node (ref "TP10") (pin "P$1") (pinfunction "1_P$1") (pintype "bidirectional"))
      (node (ref "TP5") (pin "P$1") (pinfunction "1_P$1") (pintype "bidirectional"))
      (node (ref "TP7") (pin "P$1") (pinfunction "1_P$1") (pintype "bidirectional"))
      (node (ref "TP8") (pin "P$1") (pinfunction "1_P$1") (pintype "bidirectional"))
      (node (ref "TP9") (pin "P$1") (pinfunction "1_P$1") (pintype "bidirectional"))
      (node (ref "U1") (pin "3") (pinfunction "GND_3") (pintype "power_in"))
      (node (ref "U2") (pin "3") (pinfunction "GND_3") (pintype "power_in"))
    )
    (net (code "76") (name "Net-(D1-PadA)") (class "Default")
      (node (ref "D1") (pin "A") (pinfunction "A_A") (pintype "passive"))
      (node (ref "R8") (pin "1") (pinfunction "1_1") (pintype "passive"))
    )
    (net (code "77") (name "unconnected-(J1-7-PadP$7)") (class "Default")
      (node (ref "J1") (pin "P$7") (pinfunction "7_P$7") (pintype "passive"))
    )
    (net (code "78") (name "unconnected-(J1-14-PadP$14)") (class "Default")
      (node (ref "J1") (pin "P$14") (pinfunction "14_P$14") (pintype "passive"))
    )
    (net (code "79") (name "unconnected-(J2-7-PadP$7)") (class "Default")
      (node (ref "J2") (pin "P$7") (pinfunction "7_P$7") (pintype "passive"))
    )
    (net (code "80") (name "unconnected-(J2-14-PadP$14)") (class "Default")
      (node (ref "J2") (pin "P$14") (pinfunction "14_P$14") (pintype "passive"))
    )
    (net (code "81") (name "unconnected-(J3-2-PadP$2)") (class "Default")
      (node (ref "J3") (pin "P$2") (pinfunction "2_P$2") (pintype "passive"))
    )
    (net (code "82") (name "unconnected-(J3-3-PadP$3)") (class "Default")
      (node (ref "J3") (pin "P$3") (pinfunction "3_P$3") (pintype "passive"))
    )
    (net (code "83") (name "unconnected-(J3-4-PadP$4)") (class "Default")
      (node (ref "J3") (pin "P$4") (pinfunction "4_P$4") (pintype "passive"))
    )
    (net (code "84") (name "unconnected-(J3-6-PadP$6)") (class "Default")
      (node (ref "J3") (pin "P$6") (pinfunction "6_P$6") (pintype "passive"))
    )
    (net (code "85") (name "unconnected-(J4-7-PadP$7)") (class "Default")
      (node (ref "J4") (pin "P$7") (pinfunction "7_P$7") (pintype "passive"))
    )
    (net (code "86") (name "unconnected-(J4-14-PadP$14)") (class "Default")
      (node (ref "J4") (pin "P$14") (pinfunction "14_P$14") (pintype "passive"))
    )
    (net (code "87") (name "unconnected-(J4-27-PadP$27)") (class "Default")
      (node (ref "J4") (pin "P$27") (pinfunction "27_P$27") (pintype "passive"))
    )
    (net (code "88") (name "unconnected-(J4-34-PadP$34)") (class "Default")
      (node (ref "J4") (pin "P$34") (pinfunction "34_P$34") (pintype "passive"))
    )
    (net (code "89") (name "unconnected-(J5-61-PadP$61)") (class "Default")
      (node (ref "J5") (pin "P$61") (pinfunction "61_P$61") (pintype "passive"))
    )
    (net (code "90") (name "unconnected-(R9D-1-Pad4)") (class "Default")
      (node (ref "R9") (pin "4") (pinfunction "1_4") (pintype "passive"))
    )
    (net (code "91") (name "unconnected-(R9D-2-Pad5)") (class "Default")
      (node (ref "R9") (pin "5") (pinfunction "2_5") (pintype "passive"))
    )
    (net (code "92") (name "unconnected-(R10D-1-Pad4)") (class "Default")
      (node (ref "R10") (pin "4") (pinfunction "1_4") (pintype "passive"))
    )
    (net (code "93") (name "unconnected-(R10D-2-Pad5)") (class "Default")
      (node (ref "R10") (pin "5") (pinfunction "2_5") (pintype "passive"))
    )
    (net (code "94") (name "unconnected-(R11D-1-Pad4)") (class "Default")
      (node (ref "R11") (pin "4") (pinfunction "1_4") (pintype "passive"))
    )
    (net (code "95") (name "unconnected-(R11D-2-Pad5)") (class "Default")
      (node (ref "R11") (pin "5") (pinfunction "2_5") (pintype "passive"))
    )
    (net (code "96") (name "unconnected-(R12D-1-Pad4)") (class "Default")
      (node (ref "R12") (pin "4") (pinfunction "1_4") (pintype "passive"))
    )
    (net (code "97") (name "unconnected-(R12D-2-Pad5)") (class "Default")
      (node (ref "R12") (pin "5") (pinfunction "2_5") (pintype "passive"))
    )
    (net (code "98") (name "unconnected-(R13D-1-Pad4)") (class "Default")
      (node (ref "R13") (pin "4") (pinfunction "1_4") (pintype "passive"))
    )
    (net (code "99") (name "unconnected-(R13D-2-Pad5)") (class "Default")
      (node (ref "R13") (pin "5") (pinfunction "2_5") (pintype "passive"))
    )
    (net (code "100") (name "unconnected-(R14D-1-Pad4)") (class "Default")
      (node (ref "R14") (pin "4") (pinfunction "1_4") (pintype "passive"))
    )
    (net (code "101") (name "unconnected-(R14D-2-Pad5)") (class "Default")
      (node (ref "R14") (pin "5") (pinfunction "2_5") (pintype "passive"))
    )
  )
)
